# freesoc_1_0.net
KiCad netlist of a schematic drawn in EAGLE
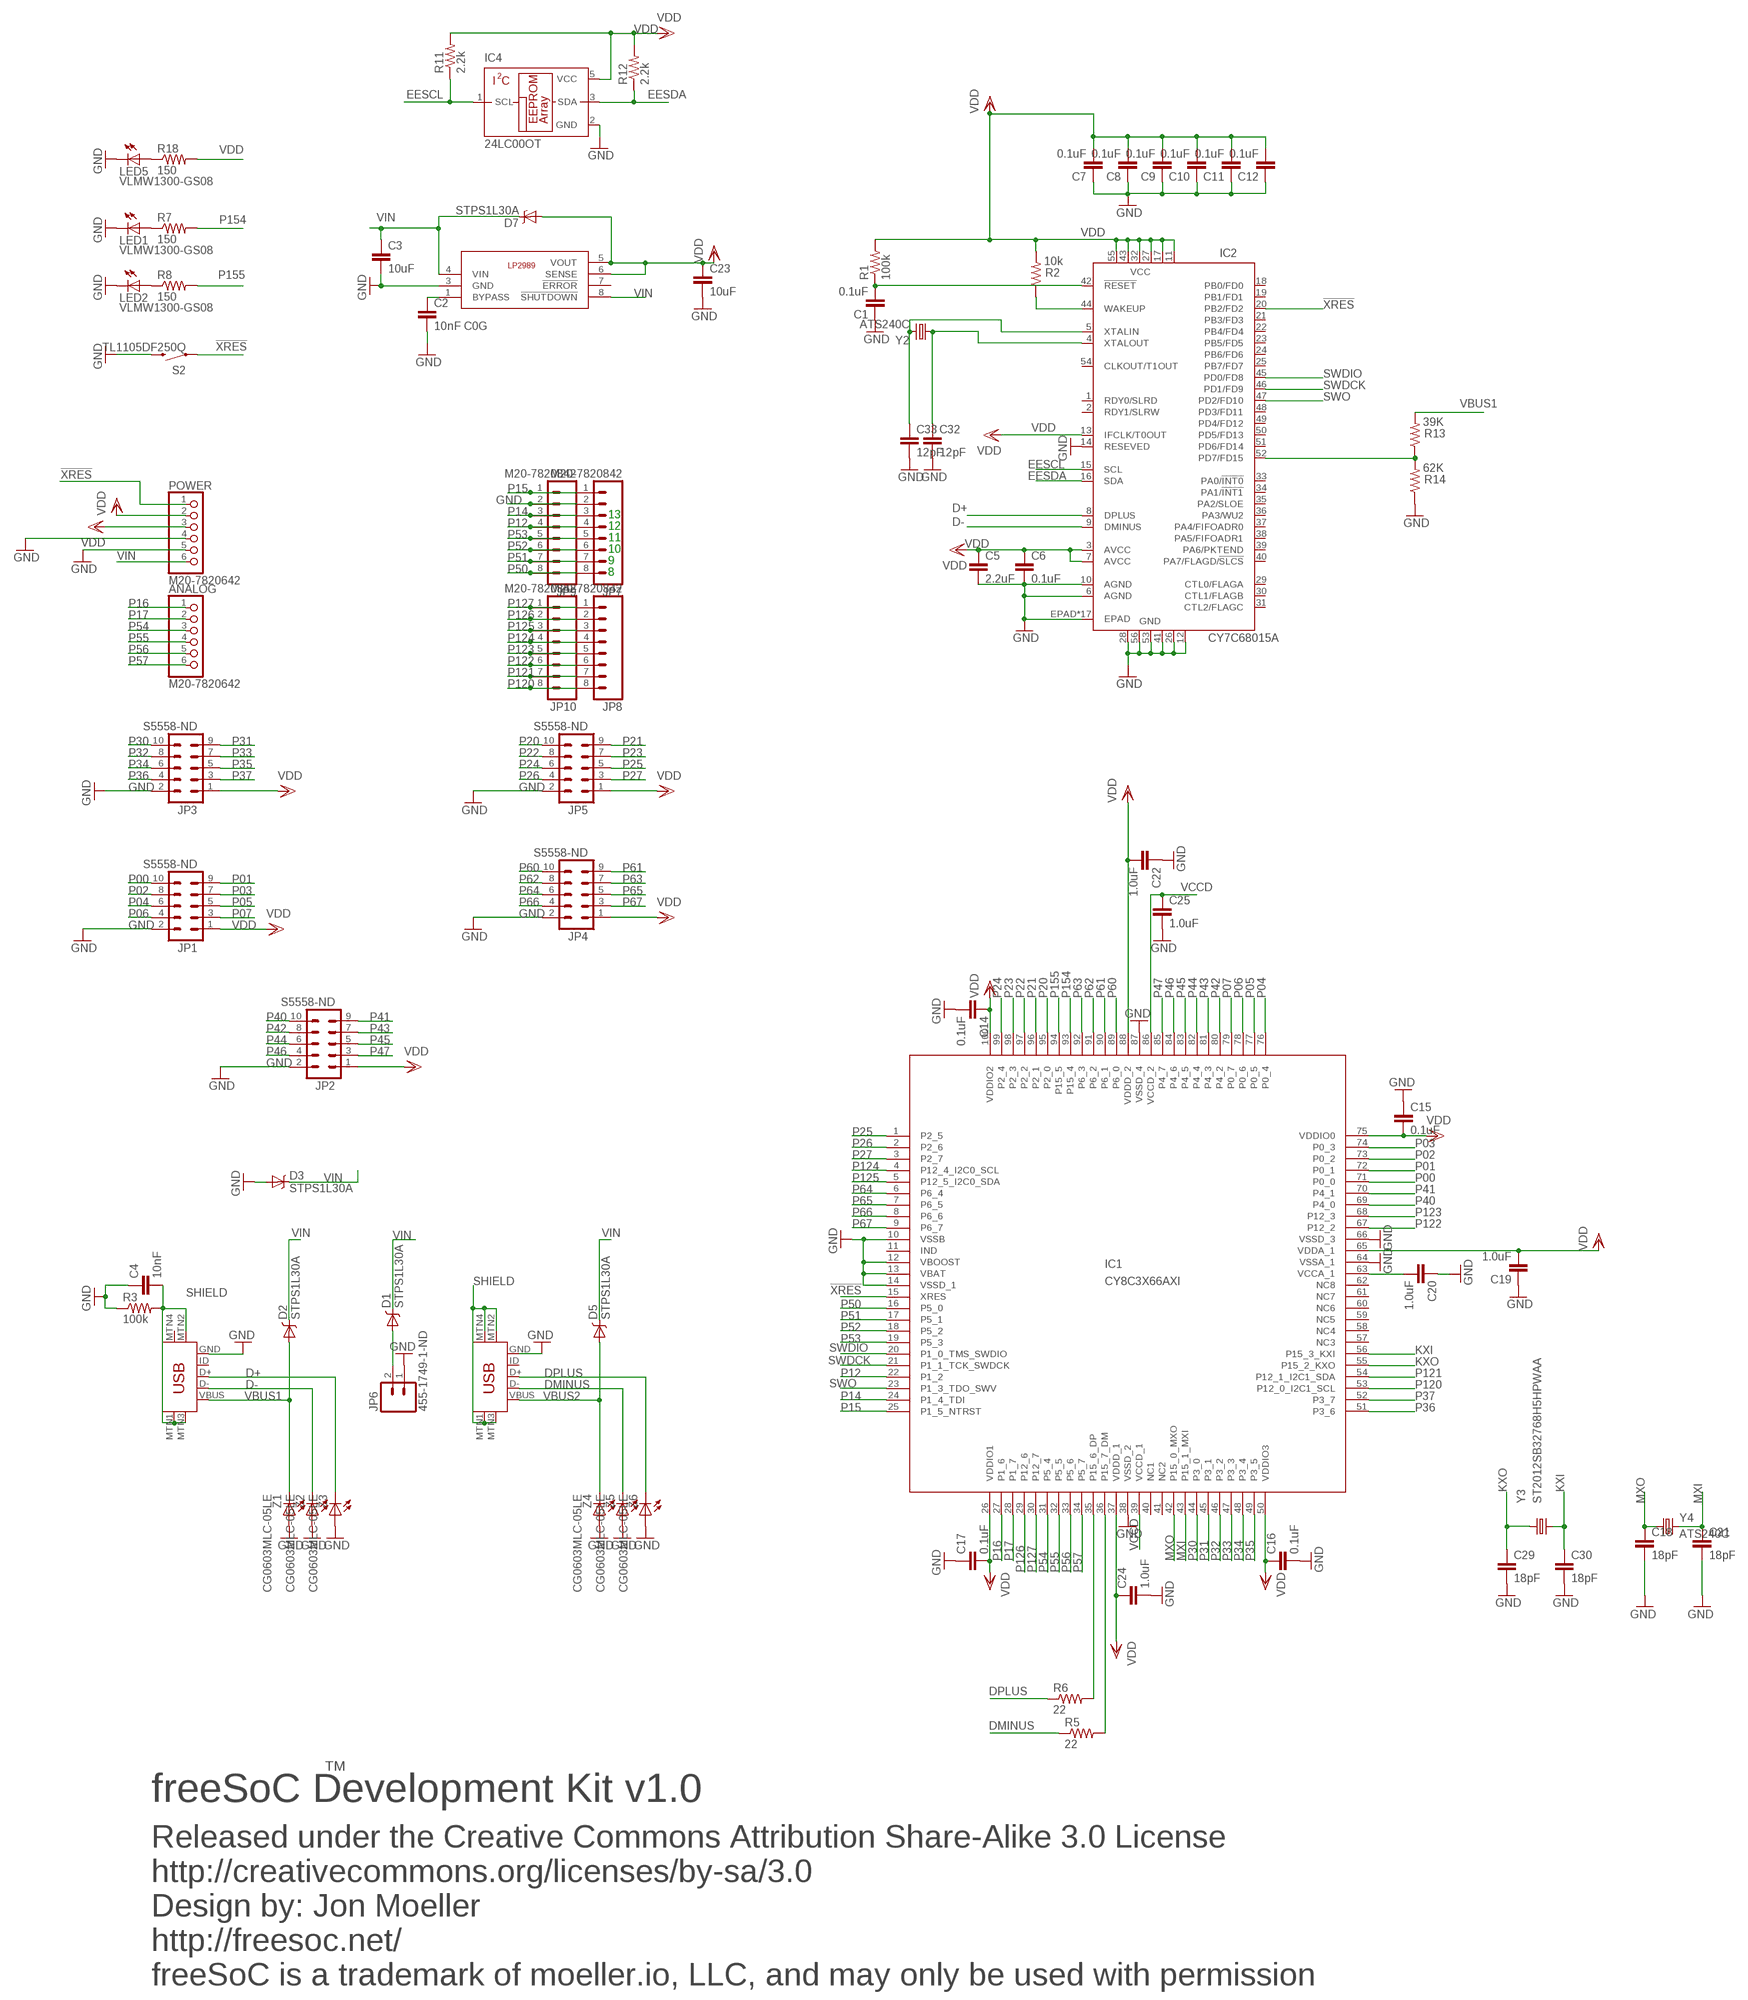
[diagram p0: schematic, sheet 1]

(export (version "E")
  (design (tool "Eeschema 10.0.6"))
  (components
    (comp (ref "ANALOG")
      (value "M20-7820642")
      (footprint "eagle-import:1X06")
      (libsource (lib "eagle-import") (part "PINHD-1X6"))
    )
    (comp (ref "C1")
      (value "0.1uF")
      (footprint "eagle-import:0402-CAP")
      (libsource (lib "eagle-import") (part "CAP0402-CAP"))
    )
    (comp (ref "C2")
      (value "10nF C0G")
      (footprint "eagle-import:0402-CAP")
      (libsource (lib "eagle-import") (part "CAP0402-CAP"))
    )
    (comp (ref "C3")
      (value "10uF")
      (footprint "eagle-import:1206")
      (libsource (lib "eagle-import") (part "CAP1206"))
    )
    (comp (ref "C4")
      (value "10nF")
      (footprint "eagle-import:0402-CAP")
      (libsource (lib "eagle-import") (part "CAP0402-CAP"))
    )
    (comp (ref "C5")
      (value "2.2uF")
      (footprint "eagle-import:0603-CAP")
      (libsource (lib "eagle-import") (part "CAP0603-CAP"))
    )
    (comp (ref "C6")
      (value "0.1uF")
      (footprint "eagle-import:0402-CAP")
      (libsource (lib "eagle-import") (part "CAP0402-CAP"))
    )
    (comp (ref "C7")
      (value "0.1uF")
      (footprint "eagle-import:0402-CAP")
      (libsource (lib "eagle-import") (part "CAP0402-CAP"))
    )
    (comp (ref "C8")
      (value "0.1uF")
      (footprint "eagle-import:0402-CAP")
      (libsource (lib "eagle-import") (part "CAP0402-CAP"))
    )
    (comp (ref "C9")
      (value "0.1uF")
      (footprint "eagle-import:0402-CAP")
      (libsource (lib "eagle-import") (part "CAP0402-CAP"))
    )
    (comp (ref "C10")
      (value "0.1uF")
      (footprint "eagle-import:0402-CAP")
      (libsource (lib "eagle-import") (part "CAP0402-CAP"))
    )
    (comp (ref "C11")
      (value "0.1uF")
      (footprint "eagle-import:0402-CAP")
      (libsource (lib "eagle-import") (part "CAP0402-CAP"))
    )
    (comp (ref "C12")
      (value "0.1uF")
      (footprint "eagle-import:0402-CAP")
      (libsource (lib "eagle-import") (part "CAP0402-CAP"))
    )
    (comp (ref "C14")
      (value "0.1uF")
      (footprint "eagle-import:0402-CAP")
      (libsource (lib "eagle-import") (part "CAP0402-CAP"))
    )
    (comp (ref "C15")
      (value "0.1uF")
      (footprint "eagle-import:0402-CAP")
      (libsource (lib "eagle-import") (part "CAP0402-CAP"))
    )
    (comp (ref "C16")
      (value "0.1uF")
      (footprint "eagle-import:0402-CAP")
      (libsource (lib "eagle-import") (part "CAP0402-CAP"))
    )
    (comp (ref "C17")
      (value "0.1uF")
      (footprint "eagle-import:0402-CAP")
      (libsource (lib "eagle-import") (part "CAP0402-CAP"))
    )
    (comp (ref "C18")
      (value "18pF")
      (footprint "eagle-import:0402-CAP")
      (libsource (lib "eagle-import") (part "CAP0402-CAP"))
    )
    (comp (ref "C19")
      (value "1.0uF")
      (footprint "eagle-import:0402-CAP")
      (libsource (lib "eagle-import") (part "CAP0402-CAP"))
    )
    (comp (ref "C20")
      (value "1.0uF")
      (footprint "eagle-import:0402-CAP")
      (libsource (lib "eagle-import") (part "CAP0402-CAP"))
    )
    (comp (ref "C21")
      (value "18pF")
      (footprint "eagle-import:0402-CAP")
      (libsource (lib "eagle-import") (part "CAP0402-CAP"))
    )
    (comp (ref "C22")
      (value "1.0uF")
      (footprint "eagle-import:0402-CAP")
      (libsource (lib "eagle-import") (part "CAP0402-CAP"))
    )
    (comp (ref "C23")
      (value "10uF")
      (footprint "eagle-import:1206")
      (libsource (lib "eagle-import") (part "CAP1206"))
    )
    (comp (ref "C24")
      (value "1.0uF")
      (footprint "eagle-import:0402-CAP")
      (libsource (lib "eagle-import") (part "CAP0402-CAP"))
    )
    (comp (ref "C25")
      (value "1.0uF")
      (footprint "eagle-import:0402-CAP")
      (libsource (lib "eagle-import") (part "CAP0402-CAP"))
    )
    (comp (ref "C29")
      (value "18pF")
      (footprint "eagle-import:0402-CAP")
      (libsource (lib "eagle-import") (part "CAP0402-CAP"))
    )
    (comp (ref "C30")
      (value "18pF")
      (footprint "eagle-import:0402-CAP")
      (libsource (lib "eagle-import") (part "CAP0402-CAP"))
    )
    (comp (ref "C32")
      (value "12pF")
      (footprint "eagle-import:0402-CAP")
      (libsource (lib "eagle-import") (part "CAP0402-CAP"))
    )
    (comp (ref "C33")
      (value "12pF")
      (footprint "eagle-import:0402-CAP")
      (libsource (lib "eagle-import") (part "CAP0402-CAP"))
    )
    (comp (ref "D1")
      (value "STPS1L30A")
      (footprint "eagle-import:SMA-DIODE")
      (libsource (lib "eagle-import") (part "DIODE-SCHOTTKY_"))
    )
    (comp (ref "D2")
      (value "STPS1L30A")
      (footprint "eagle-import:SMA-DIODE")
      (libsource (lib "eagle-import") (part "DIODE-SCHOTTKY_"))
    )
    (comp (ref "D3")
      (value "STPS1L30A")
      (footprint "eagle-import:SMA-DIODE")
      (libsource (lib "eagle-import") (part "DIODE-SCHOTTKY_"))
    )
    (comp (ref "D5")
      (value "STPS1L30A")
      (footprint "eagle-import:SMA-DIODE")
      (libsource (lib "eagle-import") (part "DIODE-SCHOTTKY_"))
    )
    (comp (ref "D7")
      (value "STPS1L30A")
      (footprint "eagle-import:SMA-DIODE")
      (libsource (lib "eagle-import") (part "DIODE-SCHOTTKY_"))
    )
    (comp (ref "IC1")
      (value "CY8C3X66AXI")
      (footprint "eagle-import:TQFP-100")
      (libsource (lib "eagle-import") (part "CY8C3X66AXI"))
    )
    (comp (ref "IC2")
      (value "CY7C68015A")
      (footprint "eagle-import:QFN56")
      (libsource (lib "eagle-import") (part "CY7C6801A-56QFNLFXC5"))
    )
    (comp (ref "IC4")
      (value "24LC00OT")
      (footprint "eagle-import:SOT23-5L")
      (libsource (lib "eagle-import") (part "2400OTLC"))
    )
    (comp (ref "JP1")
      (value "S5558-ND")
      (footprint "eagle-import:2X5-RAF")
      (libsource (lib "eagle-import") (part "M05X2RAF"))
    )
    (comp (ref "JP2")
      (value "S5558-ND")
      (footprint "eagle-import:2X5-RAF")
      (libsource (lib "eagle-import") (part "M05X2RAF"))
    )
    (comp (ref "JP3")
      (value "S5558-ND")
      (footprint "eagle-import:2X5-RAF")
      (libsource (lib "eagle-import") (part "M05X2RAF"))
    )
    (comp (ref "JP4")
      (value "S5558-ND")
      (footprint "eagle-import:2X5-RAF")
      (libsource (lib "eagle-import") (part "M05X2RAF"))
    )
    (comp (ref "JP5")
      (value "S5558-ND")
      (footprint "eagle-import:2X5-RAF")
      (libsource (lib "eagle-import") (part "M05X2RAF"))
    )
    (comp (ref "JP6")
      (value "455-1749-1-ND")
      (footprint "eagle-import:JST-2-SMD")
      (libsource (lib "eagle-import") (part "M02-JST-2MM-SMT"))
    )
    (comp (ref "JP7")
      (value "M20-7820842")
      (footprint "eagle-import:1X08")
      (libsource (lib "eagle-import") (part "M081X08"))
    )
    (comp (ref "JP8")
      (value "M20-7820842")
      (footprint "eagle-import:1X08")
      (libsource (lib "eagle-import") (part "M081X08"))
    )
    (comp (ref "JP9")
      (value "M20-7820842")
      (footprint "eagle-import:1X08")
      (libsource (lib "eagle-import") (part "M081X08"))
    )
    (comp (ref "JP10")
      (value "M20-7820842")
      (footprint "eagle-import:1X08")
      (libsource (lib "eagle-import") (part "M081X08"))
    )
    (comp (ref "LED1")
      (value "VLMW1300-GS08")
      (footprint "eagle-import:LED-0603")
      (libsource (lib "eagle-import") (part "LED0603"))
    )
    (comp (ref "LED2")
      (value "VLMW1300-GS08")
      (footprint "eagle-import:LED-0603")
      (libsource (lib "eagle-import") (part "LED0603"))
    )
    (comp (ref "LED5")
      (value "VLMW1300-GS08")
      (footprint "eagle-import:LED-0603")
      (libsource (lib "eagle-import") (part "LED0603"))
    )
    (comp (ref "POWER")
      (value "M20-7820642")
      (footprint "eagle-import:1X06")
      (libsource (lib "eagle-import") (part "PINHD-1X6"))
    )
    (comp (ref "R1")
      (value "100k")
      (footprint "eagle-import:0402-RES")
      (libsource (lib "eagle-import") (part "RESISTOR0402-RES"))
    )
    (comp (ref "R2")
      (value "10k")
      (footprint "eagle-import:0402-RES")
      (libsource (lib "eagle-import") (part "RESISTOR0402-RES"))
    )
    (comp (ref "R3")
      (value "100k")
      (footprint "eagle-import:0402-RES")
      (libsource (lib "eagle-import") (part "RESISTOR0402-RES"))
    )
    (comp (ref "R5")
      (value "22")
      (footprint "eagle-import:0805")
      (libsource (lib "eagle-import") (part "RESISTOR0805-RES"))
    )
    (comp (ref "R6")
      (value "22")
      (footprint "eagle-import:0805")
      (libsource (lib "eagle-import") (part "RESISTOR0805-RES"))
    )
    (comp (ref "R7")
      (value "150")
      (footprint "eagle-import:0603-RES")
      (libsource (lib "eagle-import") (part "RESISTOR0603-RES"))
    )
    (comp (ref "R8")
      (value "150")
      (footprint "eagle-import:0603-RES")
      (libsource (lib "eagle-import") (part "RESISTOR0603-RES"))
    )
    (comp (ref "R11")
      (value "2.2k")
      (footprint "eagle-import:0402-RES")
      (libsource (lib "eagle-import") (part "RESISTOR0402-RES"))
    )
    (comp (ref "R12")
      (value "2.2k")
      (footprint "eagle-import:0402-RES")
      (libsource (lib "eagle-import") (part "RESISTOR0402-RES"))
    )
    (comp (ref "R13")
      (value "39K")
      (footprint "eagle-import:0402-RES")
      (libsource (lib "eagle-import") (part "RESISTOR0402-RES"))
    )
    (comp (ref "R14")
      (value "62K")
      (footprint "eagle-import:0402-RES")
      (libsource (lib "eagle-import") (part "RESISTOR0402-RES"))
    )
    (comp (ref "R18")
      (value "150")
      (footprint "eagle-import:0603-RES")
      (libsource (lib "eagle-import") (part "RESISTOR0603-RES"))
    )
    (comp (ref "S2")
      (value "TL1105DF250Q")
      (footprint "eagle-import:TACTILE-PTH")
      (libsource (lib "eagle-import") (part "SWITCH-MOMENTARY-2PTH"))
    )
    (comp (ref "U$1")
      (value "LP2989")
      (footprint "eagle-import:SO08")
      (libsource (lib "eagle-import") (part "LP2989"))
    )
    (comp (ref "U$5")
      (value "USB-MINIB-5PIN")
      (footprint "eagle-import:USB-MINIB")
      (libsource (lib "eagle-import") (part "USB-MINIB-5PIN"))
    )
    (comp (ref "U$6")
      (value "USB-MINIB-5PIN")
      (footprint "eagle-import:USB-MINIB")
      (libsource (lib "eagle-import") (part "USB-MINIB-5PIN"))
    )
    (comp (ref "Y2")
      (value "ATS240C")
      (footprint "eagle-import:HC49US")
      (libsource (lib "eagle-import") (part "CRYSTALHC49US"))
    )
    (comp (ref "Y3")
      (value "ST2012SB32768H5HPWAA")
      (footprint "eagle-import:ST2012B")
      (libsource (lib "eagle-import") (part "CRYSTALST2012B"))
    )
    (comp (ref "Y4")
      (value "ATS240C")
      (footprint "eagle-import:HC49US")
      (libsource (lib "eagle-import") (part "CRYSTALHC49US"))
    )
    (comp (ref "Z1")
      (value "CG0603MLC-05LE")
      (footprint "eagle-import:LED-0603")
      (libsource (lib "eagle-import") (part "LED0603"))
    )
    (comp (ref "Z2")
      (value "CG0603MLC-05LE")
      (footprint "eagle-import:LED-0603")
      (libsource (lib "eagle-import") (part "LED0603"))
    )
    (comp (ref "Z3")
      (value "CG0603MLC-05LE")
      (footprint "eagle-import:LED-0603")
      (libsource (lib "eagle-import") (part "LED0603"))
    )
    (comp (ref "Z4")
      (value "CG0603MLC-05LE")
      (footprint "eagle-import:LED-0603")
      (libsource (lib "eagle-import") (part "LED0603"))
    )
    (comp (ref "Z5")
      (value "CG0603MLC-05LE")
      (footprint "eagle-import:LED-0603")
      (libsource (lib "eagle-import") (part "LED0603"))
    )
    (comp (ref "Z6")
      (value "CG0603MLC-05LE")
      (footprint "eagle-import:LED-0603")
      (libsource (lib "eagle-import") (part "LED0603"))
    )
  )
  (nets
    (net (code "1") (name "/D+") (class "Default")
      (node (ref "IC2") (pin "8") (pinfunction "DPLUS_8") (pintype "bidirectional"))
      (node (ref "U$5") (pin "D+") (pinfunction "D+_D+") (pintype "bidirectional"))
      (node (ref "Z3") (pin "C") (pinfunction "C_C") (pintype "passive"))
    )
    (net (code "2") (name "/D-") (class "Default")
      (node (ref "IC2") (pin "9") (pinfunction "DMINUS_9") (pintype "bidirectional"))
      (node (ref "U$5") (pin "D-") (pinfunction "D-_D-") (pintype "bidirectional"))
      (node (ref "Z2") (pin "C") (pinfunction "C_C") (pintype "passive"))
    )
    (net (code "3") (name "/DMINUS") (class "Default")
      (node (ref "R5") (pin "1") (pinfunction "1_1") (pintype "passive"))
      (node (ref "U$6") (pin "D-") (pinfunction "D-_D-") (pintype "bidirectional"))
      (node (ref "Z5") (pin "C") (pinfunction "C_C") (pintype "passive"))
    )
    (net (code "4") (name "/DPLUS") (class "Default")
      (node (ref "R6") (pin "1") (pinfunction "1_1") (pintype "passive"))
      (node (ref "U$6") (pin "D+") (pinfunction "D+_D+") (pintype "bidirectional"))
      (node (ref "Z6") (pin "C") (pinfunction "C_C") (pintype "passive"))
    )
    (net (code "5") (name "/EESCL") (class "Default")
      (node (ref "IC2") (pin "15") (pinfunction "SCL_15") (pintype "output"))
      (node (ref "IC4") (pin "1") (pinfunction "SCL_1") (pintype "input"))
      (node (ref "R11") (pin "1") (pinfunction "1_1") (pintype "passive"))
    )
    (net (code "6") (name "/EESDA") (class "Default")
      (node (ref "IC2") (pin "16") (pinfunction "SDA_16") (pintype "bidirectional"))
      (node (ref "IC4") (pin "3") (pinfunction "SDA_3") (pintype "bidirectional"))
      (node (ref "R12") (pin "1") (pinfunction "1_1") (pintype "passive"))
    )
    (net (code "7") (name "/KXI") (class "Default")
      (node (ref "C30") (pin "1") (pinfunction "1_1") (pintype "passive"))
      (node (ref "IC1") (pin "56") (pinfunction "P15_3_KXI_56") (pintype "passive"))
      (node (ref "Y3") (pin "P$2") (pinfunction "2_P$2") (pintype "passive"))
    )
    (net (code "8") (name "/KXO") (class "Default")
      (node (ref "C29") (pin "1") (pinfunction "1_1") (pintype "passive"))
      (node (ref "IC1") (pin "55") (pinfunction "P15_2_KXO_55") (pintype "passive"))
      (node (ref "Y3") (pin "P$1") (pinfunction "1_P$1") (pintype "passive"))
    )
    (net (code "9") (name "/MXI") (class "Default")
      (node (ref "C21") (pin "1") (pinfunction "1_1") (pintype "passive"))
      (node (ref "IC1") (pin "43") (pinfunction "P15_1_MXI_43") (pintype "passive"))
      (node (ref "Y4") (pin "2") (pinfunction "2_2") (pintype "passive"))
    )
    (net (code "10") (name "/MXO") (class "Default")
      (node (ref "C18") (pin "1") (pinfunction "1_1") (pintype "passive"))
      (node (ref "IC1") (pin "42") (pinfunction "P15_0_MXO_42") (pintype "passive"))
      (node (ref "Y4") (pin "1") (pinfunction "1_1") (pintype "passive"))
    )
    (net (code "11") (name "/P00") (class "Default")
      (node (ref "IC1") (pin "71") (pinfunction "P0_0_71") (pintype "passive"))
      (node (ref "JP1") (pin "10") (pinfunction "10_10") (pintype "passive"))
    )
    (net (code "12") (name "/P01") (class "Default")
      (node (ref "IC1") (pin "72") (pinfunction "P0_1_72") (pintype "passive"))
      (node (ref "JP1") (pin "9") (pinfunction "9_9") (pintype "passive"))
    )
    (net (code "13") (name "/P02") (class "Default")
      (node (ref "IC1") (pin "73") (pinfunction "P0_2_73") (pintype "passive"))
      (node (ref "JP1") (pin "8") (pinfunction "8_8") (pintype "passive"))
    )
    (net (code "14") (name "/P03") (class "Default")
      (node (ref "IC1") (pin "74") (pinfunction "P0_3_74") (pintype "passive"))
      (node (ref "JP1") (pin "7") (pinfunction "7_7") (pintype "passive"))
    )
    (net (code "15") (name "/P04") (class "Default")
      (node (ref "IC1") (pin "76") (pinfunction "P0_4_76") (pintype "passive"))
      (node (ref "JP1") (pin "6") (pinfunction "6_6") (pintype "passive"))
    )
    (net (code "16") (name "/P05") (class "Default")
      (node (ref "IC1") (pin "77") (pinfunction "P0_5_77") (pintype "passive"))
      (node (ref "JP1") (pin "5") (pinfunction "5_5") (pintype "passive"))
    )
    (net (code "17") (name "/P06") (class "Default")
      (node (ref "IC1") (pin "78") (pinfunction "P0_6_78") (pintype "passive"))
      (node (ref "JP1") (pin "4") (pinfunction "4_4") (pintype "passive"))
    )
    (net (code "18") (name "/P07") (class "Default")
      (node (ref "IC1") (pin "79") (pinfunction "P0_7_79") (pintype "passive"))
      (node (ref "JP1") (pin "3") (pinfunction "3_3") (pintype "passive"))
    )
    (net (code "19") (name "/P12") (class "Default")
      (node (ref "IC1") (pin "22") (pinfunction "P1_2_22") (pintype "passive"))
      (node (ref "JP7") (pin "4") (pinfunction "4_4") (pintype "passive"))
      (node (ref "JP9") (pin "4") (pinfunction "4_4") (pintype "passive"))
    )
    (net (code "20") (name "/P14") (class "Default")
      (node (ref "IC1") (pin "24") (pinfunction "P1_4_TDI_24") (pintype "passive"))
      (node (ref "JP7") (pin "3") (pinfunction "3_3") (pintype "passive"))
      (node (ref "JP9") (pin "3") (pinfunction "3_3") (pintype "passive"))
    )
    (net (code "21") (name "/P15") (class "Default")
      (node (ref "IC1") (pin "25") (pinfunction "P1_5_NTRST_25") (pintype "passive"))
      (node (ref "JP7") (pin "1") (pinfunction "1_1") (pintype "passive"))
      (node (ref "JP9") (pin "1") (pinfunction "1_1") (pintype "passive"))
    )
    (net (code "22") (name "/P16") (class "Default")
      (node (ref "ANALOG") (pin "1") (pinfunction "1_1") (pintype "passive"))
      (node (ref "IC1") (pin "27") (pinfunction "P1_6_27") (pintype "passive"))
    )
    (net (code "23") (name "/P17") (class "Default")
      (node (ref "ANALOG") (pin "2") (pinfunction "2_2") (pintype "passive"))
      (node (ref "IC1") (pin "28") (pinfunction "P1_7_28") (pintype "passive"))
    )
    (net (code "24") (name "/P20") (class "Default")
      (node (ref "IC1") (pin "95") (pinfunction "P2_0_95") (pintype "passive"))
      (node (ref "JP5") (pin "10") (pinfunction "10_10") (pintype "passive"))
    )
    (net (code "25") (name "/P21") (class "Default")
      (node (ref "IC1") (pin "96") (pinfunction "P2_1_96") (pintype "passive"))
      (node (ref "JP5") (pin "9") (pinfunction "9_9") (pintype "passive"))
    )
    (net (code "26") (name "/P22") (class "Default")
      (node (ref "IC1") (pin "97") (pinfunction "P2_2_97") (pintype "passive"))
      (node (ref "JP5") (pin "8") (pinfunction "8_8") (pintype "passive"))
    )
    (net (code "27") (name "/P23") (class "Default")
      (node (ref "IC1") (pin "98") (pinfunction "P2_3_98") (pintype "passive"))
      (node (ref "JP5") (pin "7") (pinfunction "7_7") (pintype "passive"))
    )
    (net (code "28") (name "/P24") (class "Default")
      (node (ref "IC1") (pin "99") (pinfunction "P2_4_99") (pintype "passive"))
      (node (ref "JP5") (pin "6") (pinfunction "6_6") (pintype "passive"))
    )
    (net (code "29") (name "/P25") (class "Default")
      (node (ref "IC1") (pin "1") (pinfunction "P2_5_1") (pintype "passive"))
      (node (ref "JP5") (pin "5") (pinfunction "5_5") (pintype "passive"))
    )
    (net (code "30") (name "/P26") (class "Default")
      (node (ref "IC1") (pin "2") (pinfunction "P2_6_2") (pintype "passive"))
      (node (ref "JP5") (pin "4") (pinfunction "4_4") (pintype "passive"))
    )
    (net (code "31") (name "/P27") (class "Default")
      (node (ref "IC1") (pin "3") (pinfunction "P2_7_3") (pintype "passive"))
      (node (ref "JP5") (pin "3") (pinfunction "3_3") (pintype "passive"))
    )
    (net (code "32") (name "/P30") (class "Default")
      (node (ref "IC1") (pin "44") (pinfunction "P3_0_44") (pintype "passive"))
      (node (ref "JP3") (pin "10") (pinfunction "10_10") (pintype "passive"))
    )
    (net (code "33") (name "/P31") (class "Default")
      (node (ref "IC1") (pin "45") (pinfunction "P3_1_45") (pintype "passive"))
      (node (ref "JP3") (pin "9") (pinfunction "9_9") (pintype "passive"))
    )
    (net (code "34") (name "/P32") (class "Default")
      (node (ref "IC1") (pin "46") (pinfunction "P3_2_46") (pintype "passive"))
      (node (ref "JP3") (pin "8") (pinfunction "8_8") (pintype "passive"))
    )
    (net (code "35") (name "/P33") (class "Default")
      (node (ref "IC1") (pin "47") (pinfunction "P3_3_47") (pintype "passive"))
      (node (ref "JP3") (pin "7") (pinfunction "7_7") (pintype "passive"))
    )
    (net (code "36") (name "/P34") (class "Default")
      (node (ref "IC1") (pin "48") (pinfunction "P3_4_48") (pintype "passive"))
      (node (ref "JP3") (pin "6") (pinfunction "6_6") (pintype "passive"))
    )
    (net (code "37") (name "/P35") (class "Default")
      (node (ref "IC1") (pin "49") (pinfunction "P3_5_49") (pintype "passive"))
      (node (ref "JP3") (pin "5") (pinfunction "5_5") (pintype "passive"))
    )
    (net (code "38") (name "/P36") (class "Default")
      (node (ref "IC1") (pin "51") (pinfunction "P3_6_51") (pintype "passive"))
      (node (ref "JP3") (pin "4") (pinfunction "4_4") (pintype "passive"))
    )
    (net (code "39") (name "/P37") (class "Default")
      (node (ref "IC1") (pin "52") (pinfunction "P3_7_52") (pintype "passive"))
      (node (ref "JP3") (pin "3") (pinfunction "3_3") (pintype "passive"))
    )
    (net (code "40") (name "/P40") (class "Default")
      (node (ref "IC1") (pin "69") (pinfunction "P4_0_69") (pintype "passive"))
      (node (ref "JP2") (pin "10") (pinfunction "10_10") (pintype "passive"))
    )
    (net (code "41") (name "/P41") (class "Default")
      (node (ref "IC1") (pin "70") (pinfunction "P4_1_70") (pintype "passive"))
      (node (ref "JP2") (pin "9") (pinfunction "9_9") (pintype "passive"))
    )
    (net (code "42") (name "/P42") (class "Default")
      (node (ref "IC1") (pin "80") (pinfunction "P4_2_80") (pintype "passive"))
      (node (ref "JP2") (pin "8") (pinfunction "8_8") (pintype "passive"))
    )
    (net (code "43") (name "/P43") (class "Default")
      (node (ref "IC1") (pin "81") (pinfunction "P4_3_81") (pintype "passive"))
      (node (ref "JP2") (pin "7") (pinfunction "7_7") (pintype "passive"))
    )
    (net (code "44") (name "/P44") (class "Default")
      (node (ref "IC1") (pin "82") (pinfunction "P4_4_82") (pintype "passive"))
      (node (ref "JP2") (pin "6") (pinfunction "6_6") (pintype "passive"))
    )
    (net (code "45") (name "/P45") (class "Default")
      (node (ref "IC1") (pin "83") (pinfunction "P4_5_83") (pintype "passive"))
      (node (ref "JP2") (pin "5") (pinfunction "5_5") (pintype "passive"))
    )
    (net (code "46") (name "/P46") (class "Default")
      (node (ref "IC1") (pin "84") (pinfunction "P4_6_84") (pintype "passive"))
      (node (ref "JP2") (pin "4") (pinfunction "4_4") (pintype "passive"))
    )
    (net (code "47") (name "/P47") (class "Default")
      (node (ref "IC1") (pin "85") (pinfunction "P4_7_85") (pintype "passive"))
      (node (ref "JP2") (pin "3") (pinfunction "3_3") (pintype "passive"))
    )
    (net (code "48") (name "/P50") (class "Default")
      (node (ref "IC1") (pin "16") (pinfunction "P5_0_16") (pintype "passive"))
      (node (ref "JP7") (pin "8") (pinfunction "8_8") (pintype "passive"))
      (node (ref "JP9") (pin "8") (pinfunction "8_8") (pintype "passive"))
    )
    (net (code "49") (name "/P51") (class "Default")
      (node (ref "IC1") (pin "17") (pinfunction "P5_1_17") (pintype "passive"))
      (node (ref "JP7") (pin "7") (pinfunction "7_7") (pintype "passive"))
      (node (ref "JP9") (pin "7") (pinfunction "7_7") (pintype "passive"))
    )
    (net (code "50") (name "/P52") (class "Default")
      (node (ref "IC1") (pin "18") (pinfunction "P5_2_18") (pintype "passive"))
      (node (ref "JP7") (pin "6") (pinfunction "6_6") (pintype "passive"))
      (node (ref "JP9") (pin "6") (pinfunction "6_6") (pintype "passive"))
    )
    (net (code "51") (name "/P53") (class "Default")
      (node (ref "IC1") (pin "19") (pinfunction "P5_3_19") (pintype "passive"))
      (node (ref "JP7") (pin "5") (pinfunction "5_5") (pintype "passive"))
      (node (ref "JP9") (pin "5") (pinfunction "5_5") (pintype "passive"))
    )
    (net (code "52") (name "/P54") (class "Default")
      (node (ref "ANALOG") (pin "3") (pinfunction "3_3") (pintype "passive"))
      (node (ref "IC1") (pin "31") (pinfunction "P5_4_31") (pintype "passive"))
    )
    (net (code "53") (name "/P55") (class "Default")
      (node (ref "ANALOG") (pin "4") (pinfunction "4_4") (pintype "passive"))
      (node (ref "IC1") (pin "32") (pinfunction "P5_5_32") (pintype "passive"))
    )
    (net (code "54") (name "/P56") (class "Default")
      (node (ref "ANALOG") (pin "5") (pinfunction "5_5") (pintype "passive"))
      (node (ref "IC1") (pin "33") (pinfunction "P5_6_33") (pintype "passive"))
    )
    (net (code "55") (name "/P57") (class "Default")
      (node (ref "ANALOG") (pin "6") (pinfunction "6_6") (pintype "passive"))
      (node (ref "IC1") (pin "34") (pinfunction "P5_7_34") (pintype "passive"))
    )
    (net (code "56") (name "/P60") (class "Default")
      (node (ref "IC1") (pin "89") (pinfunction "P6_0_89") (pintype "passive"))
      (node (ref "JP4") (pin "10") (pinfunction "10_10") (pintype "passive"))
    )
    (net (code "57") (name "/P61") (class "Default")
      (node (ref "IC1") (pin "90") (pinfunction "P6_1_90") (pintype "passive"))
      (node (ref "JP4") (pin "9") (pinfunction "9_9") (pintype "passive"))
    )
    (net (code "58") (name "/P62") (class "Default")
      (node (ref "IC1") (pin "91") (pinfunction "P6_2_91") (pintype "passive"))
      (node (ref "JP4") (pin "8") (pinfunction "8_8") (pintype "passive"))
    )
    (net (code "59") (name "/P63") (class "Default")
      (node (ref "IC1") (pin "92") (pinfunction "P6_3_92") (pintype "passive"))
      (node (ref "JP4") (pin "7") (pinfunction "7_7") (pintype "passive"))
    )
    (net (code "60") (name "/P64") (class "Default")
      (node (ref "IC1") (pin "6") (pinfunction "P6_4_6") (pintype "passive"))
      (node (ref "JP4") (pin "6") (pinfunction "6_6") (pintype "passive"))
    )
    (net (code "61") (name "/P65") (class "Default")
      (node (ref "IC1") (pin "7") (pinfunction "P6_5_7") (pintype "passive"))
      (node (ref "JP4") (pin "5") (pinfunction "5_5") (pintype "passive"))
    )
    (net (code "62") (name "/P66") (class "Default")
      (node (ref "IC1") (pin "8") (pinfunction "P6_6_8") (pintype "passive"))
      (node (ref "JP4") (pin "4") (pinfunction "4_4") (pintype "passive"))
    )
    (net (code "63") (name "/P67") (class "Default")
      (node (ref "IC1") (pin "9") (pinfunction "P6_7_9") (pintype "passive"))
      (node (ref "JP4") (pin "3") (pinfunction "3_3") (pintype "passive"))
    )
    (net (code "64") (name "/P120") (class "Default")
      (node (ref "IC1") (pin "53") (pinfunction "P12_0_I2C1_SCL_53") (pintype "passive"))
      (node (ref "JP10") (pin "8") (pinfunction "8_8") (pintype "passive"))
      (node (ref "JP8") (pin "8") (pinfunction "8_8") (pintype "passive"))
    )
    (net (code "65") (name "/P121") (class "Default")
      (node (ref "IC1") (pin "54") (pinfunction "P12_1_I2C1_SDA_54") (pintype "passive"))
      (node (ref "JP10") (pin "7") (pinfunction "7_7") (pintype "passive"))
      (node (ref "JP8") (pin "7") (pinfunction "7_7") (pintype "passive"))
    )
    (net (code "66") (name "/P122") (class "Default")
      (node (ref "IC1") (pin "67") (pinfunction "P12_2_67") (pintype "passive"))
      (node (ref "JP10") (pin "6") (pinfunction "6_6") (pintype "passive"))
      (node (ref "JP8") (pin "6") (pinfunction "6_6") (pintype "passive"))
    )
    (net (code "67") (name "/P123") (class "Default")
      (node (ref "IC1") (pin "68") (pinfunction "P12_3_68") (pintype "passive"))
      (node (ref "JP10") (pin "5") (pinfunction "5_5") (pintype "passive"))
      (node (ref "JP8") (pin "5") (pinfunction "5_5") (pintype "passive"))
    )
    (net (code "68") (name "/P124") (class "Default")
      (node (ref "IC1") (pin "4") (pinfunction "P12_4_I2C0_SCL_4") (pintype "passive"))
      (node (ref "JP10") (pin "4") (pinfunction "4_4") (pintype "passive"))
      (node (ref "JP8") (pin "4") (pinfunction "4_4") (pintype "passive"))
    )
    (net (code "69") (name "/P125") (class "Default")
      (node (ref "IC1") (pin "5") (pinfunction "P12_5_I2C0_SDA_5") (pintype "passive"))
      (node (ref "JP10") (pin "3") (pinfunction "3_3") (pintype "passive"))
      (node (ref "JP8") (pin "3") (pinfunction "3_3") (pintype "passive"))
    )
    (net (code "70") (name "/P126") (class "Default")
      (node (ref "IC1") (pin "29") (pinfunction "P12_6_29") (pintype "passive"))
      (node (ref "JP10") (pin "2") (pinfunction "2_2") (pintype "passive"))
      (node (ref "JP8") (pin "2") (pinfunction "2_2") (pintype "passive"))
    )
    (net (code "71") (name "/P127") (class "Default")
      (node (ref "IC1") (pin "30") (pinfunction "P12_7_30") (pintype "passive"))
      (node (ref "JP10") (pin "1") (pinfunction "1_1") (pintype "passive"))
      (node (ref "JP8") (pin "1") (pinfunction "1_1") (pintype "passive"))
    )
    (net (code "72") (name "/P154") (class "Default")
      (node (ref "IC1") (pin "93") (pinfunction "P15_4_93") (pintype "passive"))
      (node (ref "R7") (pin "2") (pinfunction "2_2") (pintype "passive"))
    )
    (net (code "73") (name "/P155") (class "Default")
      (node (ref "IC1") (pin "94") (pinfunction "P15_5_94") (pintype "passive"))
      (node (ref "R8") (pin "2") (pinfunction "2_2") (pintype "passive"))
    )
    (net (code "74") (name "/SHIELD") (class "Default")
      (node (ref "C4") (pin "2") (pinfunction "2_2") (pintype "passive"))
      (node (ref "R3") (pin "2") (pinfunction "2_2") (pintype "passive"))
      (node (ref "U$5") (pin "MTN1") (pinfunction "MTN2_MTN1") (pintype "bidirectional"))
      (node (ref "U$5") (pin "MTN2") (pinfunction "MTN3_MTN2") (pintype "bidirectional"))
      (node (ref "U$5") (pin "MTN3") (pinfunction "MTN1_MTN3") (pintype "bidirectional"))
      (node (ref "U$6") (pin "MTN1") (pinfunction "MTN2_MTN1") (pintype "bidirectional"))
      (node (ref "U$6") (pin "MTN2") (pinfunction "MTN3_MTN2") (pintype "bidirectional"))
      (node (ref "U$6") (pin "MTN3") (pinfunction "MTN1_MTN3") (pintype "bidirectional"))
      (node (ref "U$6") (pin "MTN4") (pinfunction "MTN4_MTN4") (pintype "bidirectional"))
    )
    (net (code "75") (name "/SWDCK") (class "Default")
      (node (ref "IC1") (pin "21") (pinfunction "P1_1_TCK_SWDCK_21") (pintype "passive"))
      (node (ref "IC2") (pin "46") (pinfunction "PD1/FD9_46") (pintype "bidirectional"))
    )
    (net (code "76") (name "/SWDIO") (class "Default")
      (node (ref "IC1") (pin "20") (pinfunction "P1_0_TMS_SWDIO_20") (pintype "passive"))
      (node (ref "IC2") (pin "45") (pinfunction "PD0/FD8_45") (pintype "bidirectional"))
    )
    (net (code "77") (name "/SWO") (class "Default")
      (node (ref "IC1") (pin "23") (pinfunction "P1_3_TDO_SWV_23") (pintype "passive"))
      (node (ref "IC2") (pin "47") (pinfunction "PD2/FD10_47") (pintype "bidirectional"))
    )
    (net (code "78") (name "/VBUS1") (class "Default")
      (node (ref "D2") (pin "A") (pinfunction "A_A") (pintype "passive"))
      (node (ref "R13") (pin "2") (pinfunction "2_2") (pintype "passive"))
      (node (ref "U$5") (pin "VBUS") (pinfunction "VBUS_VBUS") (pintype "bidirectional"))
      (node (ref "Z1") (pin "C") (pinfunction "C_C") (pintype "passive"))
    )
    (net (code "79") (name "/VBUS2") (class "Default")
      (node (ref "D5") (pin "A") (pinfunction "A_A") (pintype "passive"))
      (node (ref "U$6") (pin "VBUS") (pinfunction "VBUS_VBUS") (pintype "bidirectional"))
      (node (ref "Z4") (pin "C") (pinfunction "C_C") (pintype "passive"))
    )
    (net (code "80") (name "/VCCD") (class "Default")
      (node (ref "C25") (pin "1") (pinfunction "1_1") (pintype "passive"))
      (node (ref "IC1") (pin "39") (pinfunction "VCCD_1_39") (pintype "passive"))
      (node (ref "IC1") (pin "86") (pinfunction "VCCD_2_86") (pintype "passive"))
    )
    (net (code "81") (name "/VIN") (class "Default")
      (node (ref "C3") (pin "1") (pinfunction "1_1") (pintype "passive"))
      (node (ref "D1") (pin "C") (pinfunction "C_C") (pintype "passive"))
      (node (ref "D2") (pin "C") (pinfunction "C_C") (pintype "passive"))
      (node (ref "D3") (pin "C") (pinfunction "C_C") (pintype "passive"))
      (node (ref "D5") (pin "C") (pinfunction "C_C") (pintype "passive"))
      (node (ref "D7") (pin "C") (pinfunction "C_C") (pintype "passive"))
      (node (ref "POWER") (pin "6") (pinfunction "6_6") (pintype "passive"))
      (node (ref "U$1") (pin "4") (pinfunction "VIN_4") (pintype "bidirectional"))
      (node (ref "U$1") (pin "8") (pinfunction "~{SHUTDOWN}_8") (pintype "bidirectional"))
    )
    (net (code "82") (name "/~{XRES}") (class "Default")
      (node (ref "IC1") (pin "15") (pinfunction "XRES_15") (pintype "passive"))
      (node (ref "IC2") (pin "20") (pinfunction "PB2/FD2_20") (pintype "bidirectional"))
      (node (ref "POWER") (pin "1") (pinfunction "1_1") (pintype "passive"))
      (node (ref "S2") (pin "1") (pinfunction "1_1") (pintype "passive"))
    )
    (net (code "83") (name "GND") (class "Default")
      (node (ref "C1") (pin "1") (pinfunction "1_1") (pintype "passive"))
      (node (ref "C10") (pin "1") (pinfunction "1_1") (pintype "passive"))
      (node (ref "C11") (pin "1") (pinfunction "1_1") (pintype "passive"))
      (node (ref "C12") (pin "1") (pinfunction "1_1") (pintype "passive"))
      (node (ref "C14") (pin "2") (pinfunction "2_2") (pintype "passive"))
      (node (ref "C15") (pin "1") (pinfunction "1_1") (pintype "passive"))
      (node (ref "C16") (pin "2") (pinfunction "2_2") (pintype "passive"))
      (node (ref "C17") (pin "1") (pinfunction "1_1") (pintype "passive"))
      (node (ref "C18") (pin "2") (pinfunction "2_2") (pintype "passive"))
      (node (ref "C19") (pin "1") (pinfunction "1_1") (pintype "passive"))
      (node (ref "C2") (pin "2") (pinfunction "2_2") (pintype "passive"))
      (node (ref "C20") (pin "1") (pinfunction "1_1") (pintype "passive"))
      (node (ref "C21") (pin "2") (pinfunction "2_2") (pintype "passive"))
      (node (ref "C22") (pin "1") (pinfunction "1_1") (pintype "passive"))
      (node (ref "C23") (pin "2") (pinfunction "2_2") (pintype "passive"))
      (node (ref "C24") (pin "2") (pinfunction "2_2") (pintype "passive"))
      (node (ref "C25") (pin "2") (pinfunction "2_2") (pintype "passive"))
      (node (ref "C29") (pin "2") (pinfunction "2_2") (pintype "passive"))
      (node (ref "C3") (pin "2") (pinfunction "2_2") (pintype "passive"))
      (node (ref "C30") (pin "2") (pinfunction "2_2") (pintype "passive"))
      (node (ref "C32") (pin "2") (pinfunction "2_2") (pintype "passive"))
      (node (ref "C33") (pin "2") (pinfunction "2_2") (pintype "passive"))
      (node (ref "C4") (pin "1") (pinfunction "1_1") (pintype "passive"))
      (node (ref "C5") (pin "2") (pinfunction "2_2") (pintype "passive"))
      (node (ref "C6") (pin "2") (pinfunction "2_2") (pintype "passive"))
      (node (ref "C7") (pin "1") (pinfunction "1_1") (pintype "passive"))
      (node (ref "C8") (pin "1") (pinfunction "1_1") (pintype "passive"))
      (node (ref "C9") (pin "1") (pinfunction "1_1") (pintype "passive"))
      (node (ref "D3") (pin "A") (pinfunction "A_A") (pintype "passive"))
      (node (ref "IC1") (pin "10") (pinfunction "VSSB_10") (pintype "passive"))
      (node (ref "IC1") (pin "12") (pinfunction "VBOOST_12") (pintype "passive"))
      (node (ref "IC1") (pin "13") (pinfunction "VBAT_13") (pintype "passive"))
      (node (ref "IC1") (pin "14") (pinfunction "VSSD_1_14") (pintype "passive"))
      (node (ref "IC1") (pin "38") (pinfunction "VSSD_2_38") (pintype "passive"))
      (node (ref "IC1") (pin "64") (pinfunction "VSSA_1_64") (pintype "passive"))
      (node (ref "IC1") (pin "66") (pinfunction "VSSD_3_66") (pintype "passive"))
      (node (ref "IC1") (pin "87") (pinfunction "VSSD_4_87") (pintype "passive"))
      (node (ref "IC2") (pin "10") (pinfunction "AGND_10") (pintype "input"))
      (node (ref "IC2") (pin "12") (pinfunction "GND_12") (pintype "input"))
      (node (ref "IC2") (pin "14") (pinfunction "RESEVED_14") (pintype "input"))
      (node (ref "IC2") (pin "26") (pinfunction "GND_26") (pintype "input"))
      (node (ref "IC2") (pin "28") (pinfunction "GND_28") (pintype "input"))
      (node (ref "IC2") (pin "41") (pinfunction "GND_41") (pintype "input"))
      (node (ref "IC2") (pin "53") (pinfunction "GND_53") (pintype "input"))
      (node (ref "IC2") (pin "56") (pinfunction "GND_56") (pintype "input"))
      (node (ref "IC2") (pin "6") (pinfunction "AGND_6") (pintype "input"))
      (node (ref "IC2") (pin "EPAD") (pinfunction "EPAD_EPAD") (pintype "passive"))
      (node (ref "IC2") (pin "P$1") (pinfunction "EPAD_P$1") (pintype "passive"))
      (node (ref "IC2") (pin "P$10") (pinfunction "EPAD_P$10") (pintype "passive"))
      (node (ref "IC2") (pin "P$11") (pinfunction "EPAD_P$11") (pintype "passive"))
      (node (ref "IC2") (pin "P$12") (pinfunction "EPAD_P$12") (pintype "passive"))
      (node (ref "IC2") (pin "P$13") (pinfunction "EPAD_P$13") (pintype "passive"))
      (node (ref "IC2") (pin "P$14") (pinfunction "EPAD_P$14") (pintype "passive"))
      (node (ref "IC2") (pin "P$15") (pinfunction "EPAD_P$15") (pintype "passive"))
      (node (ref "IC2") (pin "P$16") (pinfunction "EPAD_P$16") (pintype "passive"))
      (node (ref "IC2") (pin "P$2") (pinfunction "EPAD_P$2") (pintype "passive"))
      (node (ref "IC2") (pin "P$3") (pinfunction "EPAD_P$3") (pintype "passive"))
      (node (ref "IC2") (pin "P$4") (pinfunction "EPAD_P$4") (pintype "passive"))
      (node (ref "IC2") (pin "P$5") (pinfunction "EPAD_P$5") (pintype "passive"))
      (node (ref "IC2") (pin "P$6") (pinfunction "EPAD_P$6") (pintype "passive"))
      (node (ref "IC2") (pin "P$7") (pinfunction "EPAD_P$7") (pintype "passive"))
      (node (ref "IC2") (pin "P$8") (pinfunction "EPAD_P$8") (pintype "passive"))
      (node (ref "IC2") (pin "P$9") (pinfunction "EPAD_P$9") (pintype "passive"))
      (node (ref "IC4") (pin "2") (pinfunction "GND_2") (pintype "power_in"))
      (node (ref "JP1") (pin "2") (pinfunction "2_2") (pintype "passive"))
      (node (ref "JP2") (pin "2") (pinfunction "2_2") (pintype "passive"))
      (node (ref "JP3") (pin "2") (pinfunction "2_2") (pintype "passive"))
      (node (ref "JP4") (pin "2") (pinfunction "2_2") (pintype "passive"))
      (node (ref "JP5") (pin "2") (pinfunction "2_2") (pintype "passive"))
      (node (ref "JP6") (pin "1") (pinfunction "1_1") (pintype "passive"))
      (node (ref "JP7") (pin "2") (pinfunction "2_2") (pintype "passive"))
      (node (ref "JP9") (pin "2") (pinfunction "2_2") (pintype "passive"))
      (node (ref "LED1") (pin "C") (pinfunction "C_C") (pintype "passive"))
      (node (ref "LED2") (pin "C") (pinfunction "C_C") (pintype "passive"))
      (node (ref "LED5") (pin "C") (pinfunction "C_C") (pintype "passive"))
      (node (ref "POWER") (pin "4") (pinfunction "4_4") (pintype "passive"))
      (node (ref "POWER") (pin "5") (pinfunction "5_5") (pintype "passive"))
      (node (ref "R14") (pin "1") (pinfunction "1_1") (pintype "passive"))
      (node (ref "R3") (pin "1") (pinfunction "1_1") (pintype "passive"))
      (node (ref "S2") (pin "3") (pinfunction "2_3") (pintype "passive"))
      (node (ref "U$1") (pin "3") (pinfunction "GND_3") (pintype "bidirectional"))
      (node (ref "U$5") (pin "GND") (pinfunction "GND_GND") (pintype "bidirectional"))
      (node (ref "U$6") (pin "GND") (pinfunction "GND_GND") (pintype "bidirectional"))
      (node (ref "Z1") (pin "A") (pinfunction "A_A") (pintype "passive"))
      (node (ref "Z2") (pin "A") (pinfunction "A_A") (pintype "passive"))
      (node (ref "Z3") (pin "A") (pinfunction "A_A") (pintype "passive"))
      (node (ref "Z4") (pin "A") (pinfunction "A_A") (pintype "passive"))
      (node (ref "Z5") (pin "A") (pinfunction "A_A") (pintype "passive"))
      (node (ref "Z6") (pin "A") (pinfunction "A_A") (pintype "passive"))
    )
    (net (code "84") (name "Net-(D1-PadA)") (class "Default")
      (node (ref "D1") (pin "A") (pinfunction "A_A") (pintype "passive"))
      (node (ref "JP6") (pin "2") (pinfunction "2_2") (pintype "passive"))
    )
    (net (code "85") (name "Net-(IC1-P15_6_DP)") (class "Default")
      (node (ref "IC1") (pin "35") (pinfunction "P15_6_DP_35") (pintype "passive"))
      (node (ref "R6") (pin "2") (pinfunction "2_2") (pintype "passive"))
    )
    (net (code "86") (name "Net-(IC1-P15_7_DM)") (class "Default")
      (node (ref "IC1") (pin "36") (pinfunction "P15_7_DM_36") (pintype "passive"))
      (node (ref "R5") (pin "2") (pinfunction "2_2") (pintype "passive"))
    )
    (net (code "87") (name "Net-(IC1-VCCA_1)") (class "Default")
      (node (ref "C20") (pin "2") (pinfunction "2_2") (pintype "passive"))
      (node (ref "IC1") (pin "63") (pinfunction "VCCA_1_63") (pintype "passive"))
    )
    (net (code "88") (name "Net-(IC2-PD7{slash}FD15)") (class "Default")
      (node (ref "IC2") (pin "52") (pinfunction "PD7/FD15_52") (pintype "bidirectional"))
      (node (ref "R13") (pin "1") (pinfunction "1_1") (pintype "passive"))
      (node (ref "R14") (pin "2") (pinfunction "2_2") (pintype "passive"))
    )
    (net (code "89") (name "Net-(IC2-WAKEUP)") (class "Default")
      (node (ref "IC2") (pin "44") (pinfunction "WAKEUP_44") (pintype "input"))
      (node (ref "R2") (pin "1") (pinfunction "1_1") (pintype "passive"))
    )
    (net (code "90") (name "Net-(IC2-XTALIN)") (class "Default")
      (node (ref "C33") (pin "1") (pinfunction "1_1") (pintype "passive"))
      (node (ref "IC2") (pin "5") (pinfunction "XTALIN_5") (pintype "input"))
      (node (ref "Y2") (pin "2") (pinfunction "2_2") (pintype "passive"))
    )
    (net (code "91") (name "Net-(IC2-XTALOUT)") (class "Default")
      (node (ref "C32") (pin "1") (pinfunction "1_1") (pintype "passive"))
      (node (ref "IC2") (pin "4") (pinfunction "XTALOUT_4") (pintype "input"))
      (node (ref "Y2") (pin "1") (pinfunction "1_1") (pintype "passive"))
    )
    (net (code "92") (name "Net-(IC2-~{RESET})") (class "Default")
      (node (ref "C1") (pin "2") (pinfunction "2_2") (pintype "passive"))
      (node (ref "IC2") (pin "42") (pinfunction "~{RESET}_42") (pintype "input"))
      (node (ref "R1") (pin "1") (pinfunction "1_1") (pintype "passive"))
    )
    (net (code "93") (name "Net-(LED1-PadA)") (class "Default")
      (node (ref "LED1") (pin "A") (pinfunction "A_A") (pintype "passive"))
      (node (ref "R7") (pin "1") (pinfunction "1_1") (pintype "passive"))
    )
    (net (code "94") (name "Net-(LED2-PadA)") (class "Default")
      (node (ref "LED2") (pin "A") (pinfunction "A_A") (pintype "passive"))
      (node (ref "R8") (pin "1") (pinfunction "1_1") (pintype "passive"))
    )
    (net (code "95") (name "Net-(LED5-PadA)") (class "Default")
      (node (ref "LED5") (pin "A") (pinfunction "A_A") (pintype "passive"))
      (node (ref "R18") (pin "1") (pinfunction "1_1") (pintype "passive"))
    )
    (net (code "96") (name "Net-(U$1-BYPASS)") (class "Default")
      (node (ref "C2") (pin "1") (pinfunction "1_1") (pintype "passive"))
      (node (ref "U$1") (pin "1") (pinfunction "BYPASS_1") (pintype "bidirectional"))
    )
    (net (code "97") (name "VDD") (class "Default")
      (node (ref "C10") (pin "2") (pinfunction "2_2") (pintype "passive"))
      (node (ref "C11") (pin "2") (pinfunction "2_2") (pintype "passive"))
      (node (ref "C12") (pin "2") (pinfunction "2_2") (pintype "passive"))
      (node (ref "C14") (pin "1") (pinfunction "1_1") (pintype "passive"))
      (node (ref "C15") (pin "2") (pinfunction "2_2") (pintype "passive"))
      (node (ref "C16") (pin "1") (pinfunction "1_1") (pintype "passive"))
      (node (ref "C17") (pin "2") (pinfunction "2_2") (pintype "passive"))
      (node (ref "C19") (pin "2") (pinfunction "2_2") (pintype "passive"))
      (node (ref "C22") (pin "2") (pinfunction "2_2") (pintype "passive"))
      (node (ref "C23") (pin "1") (pinfunction "1_1") (pintype "passive"))
      (node (ref "C24") (pin "1") (pinfunction "1_1") (pintype "passive"))
      (node (ref "C5") (pin "1") (pinfunction "1_1") (pintype "passive"))
      (node (ref "C6") (pin "1") (pinfunction "1_1") (pintype "passive"))
      (node (ref "C7") (pin "2") (pinfunction "2_2") (pintype "passive"))
      (node (ref "C8") (pin "2") (pinfunction "2_2") (pintype "passive"))
      (node (ref "C9") (pin "2") (pinfunction "2_2") (pintype "passive"))
      (node (ref "D7") (pin "A") (pinfunction "A_A") (pintype "passive"))
      (node (ref "IC1") (pin "100") (pinfunction "VDDIO2_100") (pintype "passive"))
      (node (ref "IC1") (pin "26") (pinfunction "VDDIO1_26") (pintype "passive"))
      (node (ref "IC1") (pin "37") (pinfunction "VDDD_1_37") (pintype "passive"))
      (node (ref "IC1") (pin "50") (pinfunction "VDDIO3_50") (pintype "passive"))
      (node (ref "IC1") (pin "65") (pinfunction "VDDA_1_65") (pintype "passive"))
      (node (ref "IC1") (pin "75") (pinfunction "VDDIO0_75") (pintype "passive"))
      (node (ref "IC1") (pin "88") (pinfunction "VDDD_2_88") (pintype "passive"))
      (node (ref "IC2") (pin "11") (pinfunction "VCC_11") (pintype "input"))
      (node (ref "IC2") (pin "13") (pinfunction "IFCLK/T0OUT_13") (pintype "bidirectional"))
      (node (ref "IC2") (pin "17") (pinfunction "VCC_17") (pintype "input"))
      (node (ref "IC2") (pin "27") (pinfunction "VCC_27") (pintype "input"))
      (node (ref "IC2") (pin "3") (pinfunction "AVCC_3") (pintype "input"))
      (node (ref "IC2") (pin "32") (pinfunction "VCC_32") (pintype "input"))
      (node (ref "IC2") (pin "43") (pinfunction "VCC_43") (pintype "input"))
      (node (ref "IC2") (pin "55") (pinfunction "VCC_55") (pintype "input"))
      (node (ref "IC2") (pin "7") (pinfunction "AVCC_7") (pintype "input"))
      (node (ref "IC4") (pin "5") (pinfunction "VCC_5") (pintype "power_in"))
      (node (ref "JP1") (pin "1") (pinfunction "1_1") (pintype "passive"))
      (node (ref "JP2") (pin "1") (pinfunction "1_1") (pintype "passive"))
      (node (ref "JP3") (pin "1") (pinfunction "1_1") (pintype "passive"))
      (node (ref "JP4") (pin "1") (pinfunction "1_1") (pintype "passive"))
      (node (ref "JP5") (pin "1") (pinfunction "1_1") (pintype "passive"))
      (node (ref "POWER") (pin "2") (pinfunction "2_2") (pintype "passive"))
      (node (ref "POWER") (pin "3") (pinfunction "3_3") (pintype "passive"))
      (node (ref "R1") (pin "2") (pinfunction "2_2") (pintype "passive"))
      (node (ref "R11") (pin "2") (pinfunction "2_2") (pintype "passive"))
      (node (ref "R12") (pin "2") (pinfunction "2_2") (pintype "passive"))
      (node (ref "R18") (pin "2") (pinfunction "2_2") (pintype "passive"))
      (node (ref "R2") (pin "2") (pinfunction "2_2") (pintype "passive"))
      (node (ref "U$1") (pin "5") (pinfunction "VOUT_5") (pintype "bidirectional"))
      (node (ref "U$1") (pin "6") (pinfunction "SENSE_6") (pintype "bidirectional"))
    )
    (net (code "98") (name "unconnected-(IC1-IND-Pad11)") (class "Default")
      (node (ref "IC1") (pin "11") (pinfunction "IND_11") (pintype "passive"))
    )
    (net (code "99") (name "unconnected-(IC1-NC1-Pad40)") (class "Default")
      (node (ref "IC1") (pin "40") (pinfunction "NC1_40") (pintype "passive"))
    )
    (net (code "100") (name "unconnected-(IC1-NC2-Pad41)") (class "Default")
      (node (ref "IC1") (pin "41") (pinfunction "NC2_41") (pintype "passive"))
    )
    (net (code "101") (name "unconnected-(IC1-NC3-Pad57)") (class "Default")
      (node (ref "IC1") (pin "57") (pinfunction "NC3_57") (pintype "passive"))
    )
    (net (code "102") (name "unconnected-(IC1-NC4-Pad58)") (class "Default")
      (node (ref "IC1") (pin "58") (pinfunction "NC4_58") (pintype "passive"))
    )
    (net (code "103") (name "unconnected-(IC1-NC5-Pad59)") (class "Default")
      (node (ref "IC1") (pin "59") (pinfunction "NC5_59") (pintype "passive"))
    )
    (net (code "104") (name "unconnected-(IC1-NC6-Pad60)") (class "Default")
      (node (ref "IC1") (pin "60") (pinfunction "NC6_60") (pintype "passive"))
    )
    (net (code "105") (name "unconnected-(IC1-NC7-Pad61)") (class "Default")
      (node (ref "IC1") (pin "61") (pinfunction "NC7_61") (pintype "passive"))
    )
    (net (code "106") (name "unconnected-(IC1-NC8-Pad62)") (class "Default")
      (node (ref "IC1") (pin "62") (pinfunction "NC8_62") (pintype "passive"))
    )
    (net (code "107") (name "unconnected-(IC2-CLKOUT{slash}T1OUT-Pad54)") (class "Default")
      (node (ref "IC2") (pin "54") (pinfunction "CLKOUT/T1OUT_54") (pintype "input"))
    )
    (net (code "108") (name "unconnected-(IC2-CTL0{slash}FLAGA-Pad29)") (class "Default")
      (node (ref "IC2") (pin "29") (pinfunction "CTL0/FLAGA_29") (pintype "output"))
    )
    (net (code "109") (name "unconnected-(IC2-CTL1{slash}FLAGB-Pad30)") (class "Default")
      (node (ref "IC2") (pin "30") (pinfunction "CTL1/FLAGB_30") (pintype "output"))
    )
    (net (code "110") (name "unconnected-(IC2-CTL2{slash}FLAGC-Pad31)") (class "Default")
      (node (ref "IC2") (pin "31") (pinfunction "CTL2/FLAGC_31") (pintype "output"))
    )
    (net (code "111") (name "unconnected-(IC2-PA0{slash}~{INT0}-Pad33)") (class "Default")
      (node (ref "IC2") (pin "33") (pinfunction "PA0/~{INT0}_33") (pintype "bidirectional"))
    )
    (net (code "112") (name "unconnected-(IC2-PA1{slash}~{INT1}-Pad34)") (class "Default")
      (node (ref "IC2") (pin "34") (pinfunction "PA1/~{INT1}_34") (pintype "bidirectional"))
    )
    (net (code "113") (name "unconnected-(IC2-PA2{slash}SLOE-Pad35)") (class "Default")
      (node (ref "IC2") (pin "35") (pinfunction "PA2/SLOE_35") (pintype "bidirectional"))
    )
    (net (code "114") (name "unconnected-(IC2-PA3{slash}WU2-Pad36)") (class "Default")
      (node (ref "IC2") (pin "36") (pinfunction "PA3/WU2_36") (pintype "bidirectional"))
    )
    (net (code "115") (name "unconnected-(IC2-PA4{slash}FIFOADR0-Pad37)") (class "Default")
      (node (ref "IC2") (pin "37") (pinfunction "PA4/FIFOADR0_37") (pintype "bidirectional"))
    )
    (net (code "116") (name "unconnected-(IC2-PA5{slash}FIFOADR1-Pad38)") (class "Default")
      (node (ref "IC2") (pin "38") (pinfunction "PA5/FIFOADR1_38") (pintype "bidirectional"))
    )
    (net (code "117") (name "unconnected-(IC2-PA6{slash}PKTEND-Pad39)") (class "Default")
      (node (ref "IC2") (pin "39") (pinfunction "PA6/PKTEND_39") (pintype "bidirectional"))
    )
    (net (code "118") (name "unconnected-(IC2-PA7{slash}FLAGD{slash}~{SLCS}-Pad40)") (class "Default")
      (node (ref "IC2") (pin "40") (pinfunction "PA7/FLAGD/~{SLCS}_40") (pintype "bidirectional"))
    )
    (net (code "119") (name "unconnected-(IC2-PB0{slash}FD0-Pad18)") (class "Default")
      (node (ref "IC2") (pin "18") (pinfunction "PB0/FD0_18") (pintype "bidirectional"))
    )
    (net (code "120") (name "unconnected-(IC2-PB1{slash}FD1-Pad19)") (class "Default")
      (node (ref "IC2") (pin "19") (pinfunction "PB1/FD1_19") (pintype "bidirectional"))
    )
    (net (code "121") (name "unconnected-(IC2-PB3{slash}FD3-Pad21)") (class "Default")
      (node (ref "IC2") (pin "21") (pinfunction "PB3/FD3_21") (pintype "bidirectional"))
    )
    (net (code "122") (name "unconnected-(IC2-PB4{slash}FD4-Pad22)") (class "Default")
      (node (ref "IC2") (pin "22") (pinfunction "PB4/FD4_22") (pintype "bidirectional"))
    )
    (net (code "123") (name "unconnected-(IC2-PB5{slash}FD5-Pad23)") (class "Default")
      (node (ref "IC2") (pin "23") (pinfunction "PB5/FD5_23") (pintype "bidirectional"))
    )
    (net (code "124") (name "unconnected-(IC2-PB6{slash}FD6-Pad24)") (class "Default")
      (node (ref "IC2") (pin "24") (pinfunction "PB6/FD6_24") (pintype "bidirectional"))
    )
    (net (code "125") (name "unconnected-(IC2-PB7{slash}FD7-Pad25)") (class "Default")
      (node (ref "IC2") (pin "25") (pinfunction "PB7/FD7_25") (pintype "bidirectional"))
    )
    (net (code "126") (name "unconnected-(IC2-PD3{slash}FD11-Pad48)") (class "Default")
      (node (ref "IC2") (pin "48") (pinfunction "PD3/FD11_48") (pintype "bidirectional"))
    )
    (net (code "127") (name "unconnected-(IC2-PD4{slash}FD12-Pad49)") (class "Default")
      (node (ref "IC2") (pin "49") (pinfunction "PD4/FD12_49") (pintype "bidirectional"))
    )
    (net (code "128") (name "unconnected-(IC2-PD5{slash}FD13-Pad50)") (class "Default")
      (node (ref "IC2") (pin "50") (pinfunction "PD5/FD13_50") (pintype "bidirectional"))
    )
    (net (code "129") (name "unconnected-(IC2-PD6{slash}FD14-Pad51)") (class "Default")
      (node (ref "IC2") (pin "51") (pinfunction "PD6/FD14_51") (pintype "bidirectional"))
    )
    (net (code "130") (name "unconnected-(IC2-RDY0{slash}SLRD-Pad1)") (class "Default")
      (node (ref "IC2") (pin "1") (pinfunction "RDY0/SLRD_1") (pintype "input"))
    )
    (net (code "131") (name "unconnected-(IC2-RDY1{slash}SLRW-Pad2)") (class "Default")
      (node (ref "IC2") (pin "2") (pinfunction "RDY1/SLRW_2") (pintype "input"))
    )
    (net (code "132") (name "unconnected-(U$1-~{ERROR}-Pad7)") (class "Default")
      (node (ref "U$1") (pin "7") (pinfunction "~{ERROR}_7") (pintype "bidirectional"))
    )
    (net (code "133") (name "unconnected-(U$5-PadID)") (class "Default")
      (node (ref "U$5") (pin "ID") (pinfunction "ID_ID") (pintype "bidirectional"))
    )
    (net (code "134") (name "unconnected-(U$5-PadMTN4)") (class "Default")
      (node (ref "U$5") (pin "MTN4") (pinfunction "MTN4_MTN4") (pintype "bidirectional"))
    )
    (net (code "135") (name "unconnected-(U$6-PadID)") (class "Default")
      (node (ref "U$6") (pin "ID") (pinfunction "ID_ID") (pintype "bidirectional"))
    )
  )
)
